# Generador_de_funciones.net
KiCad netlist of a schematic drawn in EAGLE
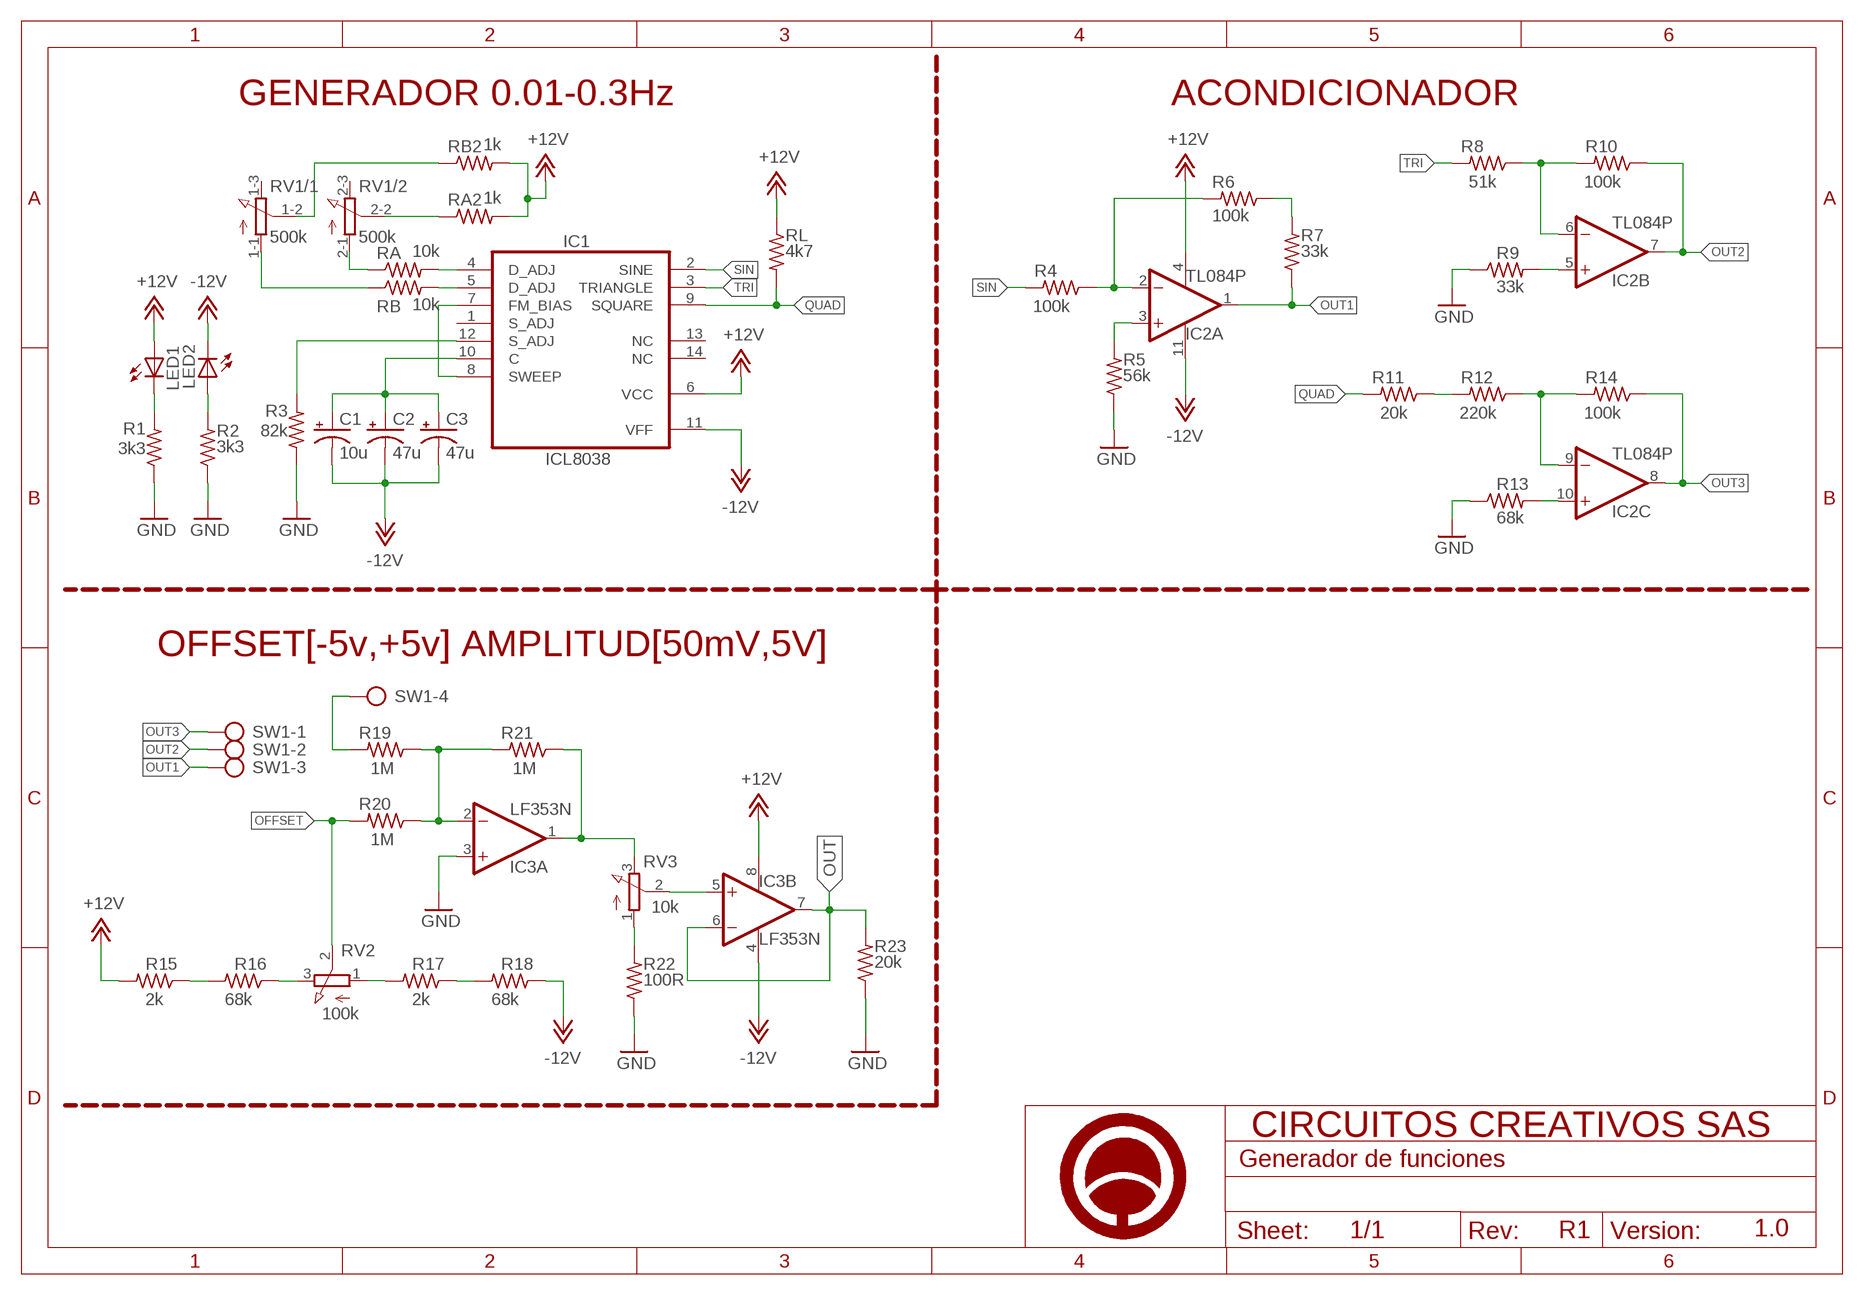
[diagram p0: schematic, sheet 1]

(export (version "E")
  (design (tool "Eeschema 10.0.6"))
  (components
    (comp (ref "C1")
      (value "10u")
      (footprint "eagle-import:E2-5")
      (libsource (lib "eagle-import") (part "CPOL-USE2-5"))
    )
    (comp (ref "C2")
      (value "47u")
      (footprint "eagle-import:E2-5")
      (libsource (lib "eagle-import") (part "CPOL-USE2-5"))
    )
    (comp (ref "C3")
      (value "47u")
      (footprint "eagle-import:E2-5")
      (libsource (lib "eagle-import") (part "CPOL-USE2-5"))
    )
    (comp (ref "FRAME1")
      (value "A4_HORIZONTAL")
      (footprint "eagle-import:LOGO")
      (libsource (lib "eagle-import") (part "A4_HORIZONTAL"))
    )
    (comp (ref "IC1")
      (value "ICL8038")
      (footprint "eagle-import:DIL14")
      (libsource (lib "eagle-import") (part "XR-8038"))
    )
    (comp (ref "IC2")
      (value "TL084P")
      (footprint "eagle-import:DIL14")
      (libsource (lib "eagle-import") (part "TL084P"))
    )
    (comp (ref "IC3")
      (value "LF353N")
      (footprint "eagle-import:DIL08")
      (libsource (lib "eagle-import") (part "LF353N"))
    )
    (comp (ref "LED1")
      (value "LED3MM")
      (footprint "eagle-import:LED3MM")
      (libsource (lib "eagle-import") (part "LED3MM"))
    )
    (comp (ref "LED2")
      (value "LED3MM")
      (footprint "eagle-import:LED3MM")
      (libsource (lib "eagle-import") (part "LED3MM"))
    )
    (comp (ref "R1")
      (value "3k3")
      (footprint "eagle-import:0204_7")
      (libsource (lib "eagle-import") (part "R-US_0204/7"))
    )
    (comp (ref "R2")
      (value "3k3")
      (footprint "eagle-import:0204_7")
      (libsource (lib "eagle-import") (part "R-US_0204/7"))
    )
    (comp (ref "R3")
      (value "82k")
      (footprint "eagle-import:0204_7")
      (libsource (lib "eagle-import") (part "R-US_0204/7"))
    )
    (comp (ref "R4")
      (value "100k")
      (footprint "eagle-import:0204_7")
      (libsource (lib "eagle-import") (part "R-US_0204/7"))
    )
    (comp (ref "R5")
      (value "56k")
      (footprint "eagle-import:0204_7")
      (libsource (lib "eagle-import") (part "R-US_0204/7"))
    )
    (comp (ref "R6")
      (value "100k")
      (footprint "eagle-import:0204_7")
      (libsource (lib "eagle-import") (part "R-US_0204/7"))
    )
    (comp (ref "R7")
      (value "33k")
      (footprint "eagle-import:0204_7")
      (libsource (lib "eagle-import") (part "R-US_0204/7"))
    )
    (comp (ref "R8")
      (value "51k")
      (footprint "eagle-import:0204_7")
      (libsource (lib "eagle-import") (part "R-US_0204/7"))
    )
    (comp (ref "R9")
      (value "33k")
      (footprint "eagle-import:0204_7")
      (libsource (lib "eagle-import") (part "R-US_0204/7"))
    )
    (comp (ref "R10")
      (value "100k")
      (footprint "eagle-import:0204_7")
      (libsource (lib "eagle-import") (part "R-US_0204/7"))
    )
    (comp (ref "R11")
      (value "20k")
      (footprint "eagle-import:0204_7")
      (libsource (lib "eagle-import") (part "R-US_0204/7"))
    )
    (comp (ref "R12")
      (value "220k")
      (footprint "eagle-import:0204_7")
      (libsource (lib "eagle-import") (part "R-US_0204/7"))
    )
    (comp (ref "R13")
      (value "68k")
      (footprint "eagle-import:0204_7")
      (libsource (lib "eagle-import") (part "R-US_0204/7"))
    )
    (comp (ref "R14")
      (value "100k")
      (footprint "eagle-import:0204_7")
      (libsource (lib "eagle-import") (part "R-US_0204/7"))
    )
    (comp (ref "R15")
      (value "2k")
      (footprint "eagle-import:0204_7")
      (libsource (lib "eagle-import") (part "R-US_0204/7"))
    )
    (comp (ref "R16")
      (value "68k")
      (footprint "eagle-import:0204_7")
      (libsource (lib "eagle-import") (part "R-US_0204/7"))
    )
    (comp (ref "R17")
      (value "2k")
      (footprint "eagle-import:0204_7")
      (libsource (lib "eagle-import") (part "R-US_0204/7"))
    )
    (comp (ref "R18")
      (value "68k")
      (footprint "eagle-import:0204_7")
      (libsource (lib "eagle-import") (part "R-US_0204/7"))
    )
    (comp (ref "R19")
      (value "1M")
      (footprint "eagle-import:0204_7")
      (libsource (lib "eagle-import") (part "R-US_0204/7"))
    )
    (comp (ref "R20")
      (value "1M")
      (footprint "eagle-import:0204_7")
      (libsource (lib "eagle-import") (part "R-US_0204/7"))
    )
    (comp (ref "R21")
      (value "1M")
      (footprint "eagle-import:0204_7")
      (libsource (lib "eagle-import") (part "R-US_0204/7"))
    )
    (comp (ref "R22")
      (value "100R")
      (footprint "eagle-import:0204_7")
      (libsource (lib "eagle-import") (part "R-US_0204/7"))
    )
    (comp (ref "R23")
      (value "20k")
      (footprint "eagle-import:0204_7")
      (libsource (lib "eagle-import") (part "R-US_0204/7"))
    )
    (comp (ref "RA")
      (value "10k")
      (footprint "eagle-import:0204_7")
      (libsource (lib "eagle-import") (part "R-US_0204/7"))
    )
    (comp (ref "RA2")
      (value "1k")
      (footprint "eagle-import:0204_7")
      (libsource (lib "eagle-import") (part "R-US_0204/7"))
    )
    (comp (ref "RB")
      (value "10k")
      (footprint "eagle-import:0204_7")
      (libsource (lib "eagle-import") (part "R-US_0204/7"))
    )
    (comp (ref "RB2")
      (value "1k")
      (footprint "eagle-import:0204_7")
      (libsource (lib "eagle-import") (part "R-US_0204/7"))
    )
    (comp (ref "RL")
      (value "4k7")
      (footprint "eagle-import:0204_7")
      (libsource (lib "eagle-import") (part "R-US_0204/7"))
    )
    (comp (ref "RV1")
      (value "500k")
      (footprint "eagle-import:3RP_1610G")
      (libsource (lib "eagle-import") (part "3RP/1610G"))
    )
    (comp (ref "RV2")
      (value "100k")
      (footprint "eagle-import:3RP_1610N")
      (libsource (lib "eagle-import") (part "3RP/1610N"))
    )
    (comp (ref "RV3")
      (value "10k")
      (footprint "eagle-import:3RP_1610N")
      (libsource (lib "eagle-import") (part "3RP/1610N"))
    )
    (comp (ref "SW1")
      (value "AK500/4")
      (footprint "eagle-import:AK500_4")
      (libsource (lib "eagle-import") (part "AK500/4"))
    )
  )
  (nets
    (net (code "1") (name "+12V") (class "Default")
      (node (ref "IC1") (pin "6") (pinfunction "VCC_6") (pintype "power_in"))
      (node (ref "IC2") (pin "4") (pinfunction "V+_4") (pintype "power_in"))
      (node (ref "IC3") (pin "8") (pinfunction "V+_8") (pintype "power_in"))
      (node (ref "LED1") (pin "A") (pinfunction "A_A") (pintype "passive"))
      (node (ref "R15") (pin "2") (pinfunction "2_2") (pintype "passive"))
      (node (ref "RA2") (pin "2") (pinfunction "2_2") (pintype "passive"))
      (node (ref "RB2") (pin "2") (pinfunction "2_2") (pintype "passive"))
      (node (ref "RL") (pin "1") (pinfunction "1_1") (pintype "passive"))
    )
    (net (code "2") (name "-12V") (class "Default")
      (node (ref "C1") (pin "-") (pinfunction "-_-") (pintype "passive"))
      (node (ref "C2") (pin "-") (pinfunction "-_-") (pintype "passive"))
      (node (ref "C3") (pin "-") (pinfunction "-_-") (pintype "passive"))
      (node (ref "IC1") (pin "11") (pinfunction "VFF_11") (pintype "power_in"))
      (node (ref "IC2") (pin "11") (pinfunction "V-_11") (pintype "power_in"))
      (node (ref "IC3") (pin "4") (pinfunction "V-_4") (pintype "power_in"))
      (node (ref "LED2") (pin "K") (pinfunction "C_K") (pintype "passive"))
      (node (ref "R18") (pin "1") (pinfunction "1_1") (pintype "passive"))
    )
    (net (code "3") (name "GND") (class "Default")
      (node (ref "IC3") (pin "3") (pinfunction "+IN_3") (pintype "input"))
      (node (ref "R1") (pin "1") (pinfunction "1_1") (pintype "passive"))
      (node (ref "R13") (pin "1") (pinfunction "1_1") (pintype "passive"))
      (node (ref "R2") (pin "1") (pinfunction "1_1") (pintype "passive"))
      (node (ref "R22") (pin "1") (pinfunction "1_1") (pintype "passive"))
      (node (ref "R23") (pin "1") (pinfunction "1_1") (pintype "passive"))
      (node (ref "R3") (pin "1") (pinfunction "1_1") (pintype "passive"))
      (node (ref "R5") (pin "1") (pinfunction "1_1") (pintype "passive"))
      (node (ref "R9") (pin "1") (pinfunction "1_1") (pintype "passive"))
    )
    (net (code "4") (name "Net-(IC1-C)") (class "Default")
      (node (ref "C1") (pin "+") (pinfunction "+_+") (pintype "passive"))
      (node (ref "C2") (pin "+") (pinfunction "+_+") (pintype "passive"))
      (node (ref "C3") (pin "+") (pinfunction "+_+") (pintype "passive"))
      (node (ref "IC1") (pin "10") (pinfunction "C_10") (pintype "input"))
    )
    (net (code "5") (name "Net-(IC1-D_ADJ-Pad4)") (class "Default")
      (node (ref "IC1") (pin "4") (pinfunction "D_ADJ_4") (pintype "input"))
      (node (ref "RA") (pin "2") (pinfunction "2_2") (pintype "passive"))
    )
    (net (code "6") (name "Net-(IC1-D_ADJ-Pad5)") (class "Default")
      (node (ref "IC1") (pin "5") (pinfunction "D_ADJ_5") (pintype "input"))
      (node (ref "RB") (pin "2") (pinfunction "2_2") (pintype "passive"))
    )
    (net (code "7") (name "Net-(IC1-FM_BIAS)") (class "Default")
      (node (ref "IC1") (pin "7") (pinfunction "FM_BIAS_7") (pintype "input"))
      (node (ref "IC1") (pin "8") (pinfunction "SWEEP_8") (pintype "input"))
    )
    (net (code "8") (name "Net-(IC1-S_ADJ-Pad12)") (class "Default")
      (node (ref "IC1") (pin "12") (pinfunction "S_ADJ_12") (pintype "input"))
      (node (ref "R3") (pin "2") (pinfunction "2_2") (pintype "passive"))
    )
    (net (code "9") (name "Net-(IC2A-+IN)") (class "Default")
      (node (ref "IC2") (pin "3") (pinfunction "+IN_3") (pintype "input"))
      (node (ref "R5") (pin "2") (pinfunction "2_2") (pintype "passive"))
    )
    (net (code "10") (name "Net-(IC2A--IN)") (class "Default")
      (node (ref "IC2") (pin "2") (pinfunction "-IN_2") (pintype "input"))
      (node (ref "R4") (pin "1") (pinfunction "1_1") (pintype "passive"))
      (node (ref "R6") (pin "2") (pinfunction "2_2") (pintype "passive"))
    )
    (net (code "11") (name "Net-(IC2B-+IN)") (class "Default")
      (node (ref "IC2") (pin "5") (pinfunction "+IN_5") (pintype "input"))
      (node (ref "R9") (pin "2") (pinfunction "2_2") (pintype "passive"))
    )
    (net (code "12") (name "Net-(IC2B--IN)") (class "Default")
      (node (ref "IC2") (pin "6") (pinfunction "-IN_6") (pintype "input"))
      (node (ref "R10") (pin "2") (pinfunction "2_2") (pintype "passive"))
      (node (ref "R8") (pin "1") (pinfunction "1_1") (pintype "passive"))
    )
    (net (code "13") (name "Net-(IC2C-+IN)") (class "Default")
      (node (ref "IC2") (pin "10") (pinfunction "+IN_10") (pintype "input"))
      (node (ref "R13") (pin "2") (pinfunction "2_2") (pintype "passive"))
    )
    (net (code "14") (name "Net-(IC2C--IN)") (class "Default")
      (node (ref "IC2") (pin "9") (pinfunction "-IN_9") (pintype "input"))
      (node (ref "R12") (pin "1") (pinfunction "1_1") (pintype "passive"))
      (node (ref "R14") (pin "2") (pinfunction "2_2") (pintype "passive"))
    )
    (net (code "15") (name "Net-(IC3A--IN)") (class "Default")
      (node (ref "IC3") (pin "2") (pinfunction "-IN_2") (pintype "input"))
      (node (ref "R19") (pin "1") (pinfunction "1_1") (pintype "passive"))
      (node (ref "R20") (pin "1") (pinfunction "1_1") (pintype "passive"))
      (node (ref "R21") (pin "2") (pinfunction "2_2") (pintype "passive"))
    )
    (net (code "16") (name "Net-(IC3A-OUT)") (class "Default")
      (node (ref "IC3") (pin "1") (pinfunction "OUT_1") (pintype "output"))
      (node (ref "R21") (pin "1") (pinfunction "1_1") (pintype "passive"))
      (node (ref "RV3") (pin "3") (pinfunction "E_3") (pintype "passive"))
    )
    (net (code "17") (name "Net-(IC3B-+IN)") (class "Default")
      (node (ref "IC3") (pin "5") (pinfunction "+IN_5") (pintype "input"))
      (node (ref "RV3") (pin "2") (pinfunction "S_2") (pintype "passive"))
    )
    (net (code "18") (name "Net-(LED1-C)") (class "Default")
      (node (ref "LED1") (pin "K") (pinfunction "C_K") (pintype "passive"))
      (node (ref "R1") (pin "2") (pinfunction "2_2") (pintype "passive"))
    )
    (net (code "19") (name "Net-(LED2-PadA)") (class "Default")
      (node (ref "LED2") (pin "A") (pinfunction "A_A") (pintype "passive"))
      (node (ref "R2") (pin "2") (pinfunction "2_2") (pintype "passive"))
    )
    (net (code "20") (name "Net-(R6-Pad1)") (class "Default")
      (node (ref "R6") (pin "1") (pinfunction "1_1") (pintype "passive"))
      (node (ref "R7") (pin "2") (pinfunction "2_2") (pintype "passive"))
    )
    (net (code "21") (name "Net-(R11-Pad1)") (class "Default")
      (node (ref "R11") (pin "1") (pinfunction "1_1") (pintype "passive"))
      (node (ref "R12") (pin "2") (pinfunction "2_2") (pintype "passive"))
    )
    (net (code "22") (name "Net-(R15-Pad1)") (class "Default")
      (node (ref "R15") (pin "1") (pinfunction "1_1") (pintype "passive"))
      (node (ref "R16") (pin "2") (pinfunction "2_2") (pintype "passive"))
    )
    (net (code "23") (name "Net-(R17-Pad1)") (class "Default")
      (node (ref "R17") (pin "1") (pinfunction "1_1") (pintype "passive"))
      (node (ref "R18") (pin "2") (pinfunction "2_2") (pintype "passive"))
    )
    (net (code "24") (name "Net-(RV1A-A)") (class "Default")
      (node (ref "RB") (pin "1") (pinfunction "1_1") (pintype "passive"))
      (node (ref "RV1") (pin "1-1") (pinfunction "A_1-1") (pintype "passive"))
    )
    (net (code "25") (name "Net-(RV1A-S)") (class "Default")
      (node (ref "RB2") (pin "1") (pinfunction "1_1") (pintype "passive"))
      (node (ref "RV1") (pin "1-2") (pinfunction "S_1-2") (pintype "passive"))
    )
    (net (code "26") (name "Net-(RV1B-A)") (class "Default")
      (node (ref "RA") (pin "1") (pinfunction "1_1") (pintype "passive"))
      (node (ref "RV1") (pin "2-1") (pinfunction "A_2-1") (pintype "passive"))
    )
    (net (code "27") (name "Net-(RV1B-S)") (class "Default")
      (node (ref "RA2") (pin "1") (pinfunction "1_1") (pintype "passive"))
      (node (ref "RV1") (pin "2-2") (pinfunction "S_2-2") (pintype "passive"))
    )
    (net (code "28") (name "Net-(RV2-A)") (class "Default")
      (node (ref "R17") (pin "2") (pinfunction "2_2") (pintype "passive"))
      (node (ref "RV2") (pin "1") (pinfunction "A_1") (pintype "passive"))
    )
    (net (code "29") (name "Net-(RV2-E)") (class "Default")
      (node (ref "R16") (pin "1") (pinfunction "1_1") (pintype "passive"))
      (node (ref "RV2") (pin "3") (pinfunction "E_3") (pintype "passive"))
    )
    (net (code "30") (name "Net-(RV3-A)") (class "Default")
      (node (ref "R22") (pin "2") (pinfunction "2_2") (pintype "passive"))
      (node (ref "RV3") (pin "1") (pinfunction "A_1") (pintype "passive"))
    )
    (net (code "31") (name "Net-(SW1D-KL)") (class "Default")
      (node (ref "R19") (pin "2") (pinfunction "2_2") (pintype "passive"))
      (node (ref "SW1") (pin "4") (pinfunction "KL_4") (pintype "passive"))
    )
    (net (code "32") (name "OFFSET") (class "Default")
      (node (ref "R20") (pin "2") (pinfunction "2_2") (pintype "passive"))
      (node (ref "RV2") (pin "2") (pinfunction "S_2") (pintype "passive"))
    )
    (net (code "33") (name "OUT") (class "Default")
      (node (ref "IC3") (pin "6") (pinfunction "-IN_6") (pintype "input"))
      (node (ref "IC3") (pin "7") (pinfunction "OUT_7") (pintype "output"))
      (node (ref "R23") (pin "2") (pinfunction "2_2") (pintype "passive"))
    )
    (net (code "34") (name "OUT1") (class "Default")
      (node (ref "IC2") (pin "1") (pinfunction "OUT_1") (pintype "output"))
      (node (ref "R7") (pin "1") (pinfunction "1_1") (pintype "passive"))
      (node (ref "SW1") (pin "3") (pinfunction "KL_3") (pintype "passive"))
    )
    (net (code "35") (name "OUT2") (class "Default")
      (node (ref "IC2") (pin "7") (pinfunction "OUT_7") (pintype "output"))
      (node (ref "R10") (pin "1") (pinfunction "1_1") (pintype "passive"))
      (node (ref "SW1") (pin "2") (pinfunction "KL_2") (pintype "passive"))
    )
    (net (code "36") (name "OUT3") (class "Default")
      (node (ref "IC2") (pin "8") (pinfunction "OUT_8") (pintype "output"))
      (node (ref "R14") (pin "1") (pinfunction "1_1") (pintype "passive"))
      (node (ref "SW1") (pin "1") (pinfunction "KL_1") (pintype "passive"))
    )
    (net (code "37") (name "QUAD") (class "Default")
      (node (ref "IC1") (pin "9") (pinfunction "SQUARE_9") (pintype "output"))
      (node (ref "R11") (pin "2") (pinfunction "2_2") (pintype "passive"))
      (node (ref "RL") (pin "2") (pinfunction "2_2") (pintype "passive"))
    )
    (net (code "38") (name "SIN") (class "Default")
      (node (ref "IC1") (pin "2") (pinfunction "SINE_2") (pintype "output"))
      (node (ref "R4") (pin "2") (pinfunction "2_2") (pintype "passive"))
    )
    (net (code "39") (name "TRI") (class "Default")
      (node (ref "IC1") (pin "3") (pinfunction "TRIANGLE_3") (pintype "output"))
      (node (ref "R8") (pin "2") (pinfunction "2_2") (pintype "passive"))
    )
    (net (code "40") (name "unconnected-(IC1-NC-Pad13)") (class "Default")
      (node (ref "IC1") (pin "13") (pinfunction "NC_13") (pintype "no_connect"))
    )
    (net (code "41") (name "unconnected-(IC1-NC-Pad14)") (class "Default")
      (node (ref "IC1") (pin "14") (pinfunction "NC_14") (pintype "no_connect"))
    )
    (net (code "42") (name "unconnected-(IC1-S_ADJ-Pad1)") (class "Default")
      (node (ref "IC1") (pin "1") (pinfunction "S_ADJ_1") (pintype "input"))
    )
    (net (code "43") (name "unconnected-(RV1A-E-Pad1-3)") (class "Default")
      (node (ref "RV1") (pin "1-3") (pinfunction "E_1-3") (pintype "passive"))
    )
    (net (code "44") (name "unconnected-(RV1B-E-Pad2-3)") (class "Default")
      (node (ref "RV1") (pin "2-3") (pinfunction "E_2-3") (pintype "passive"))
    )
  )
)
